# design.net
KiCad netlist of a schematic drawn in Altium Designer
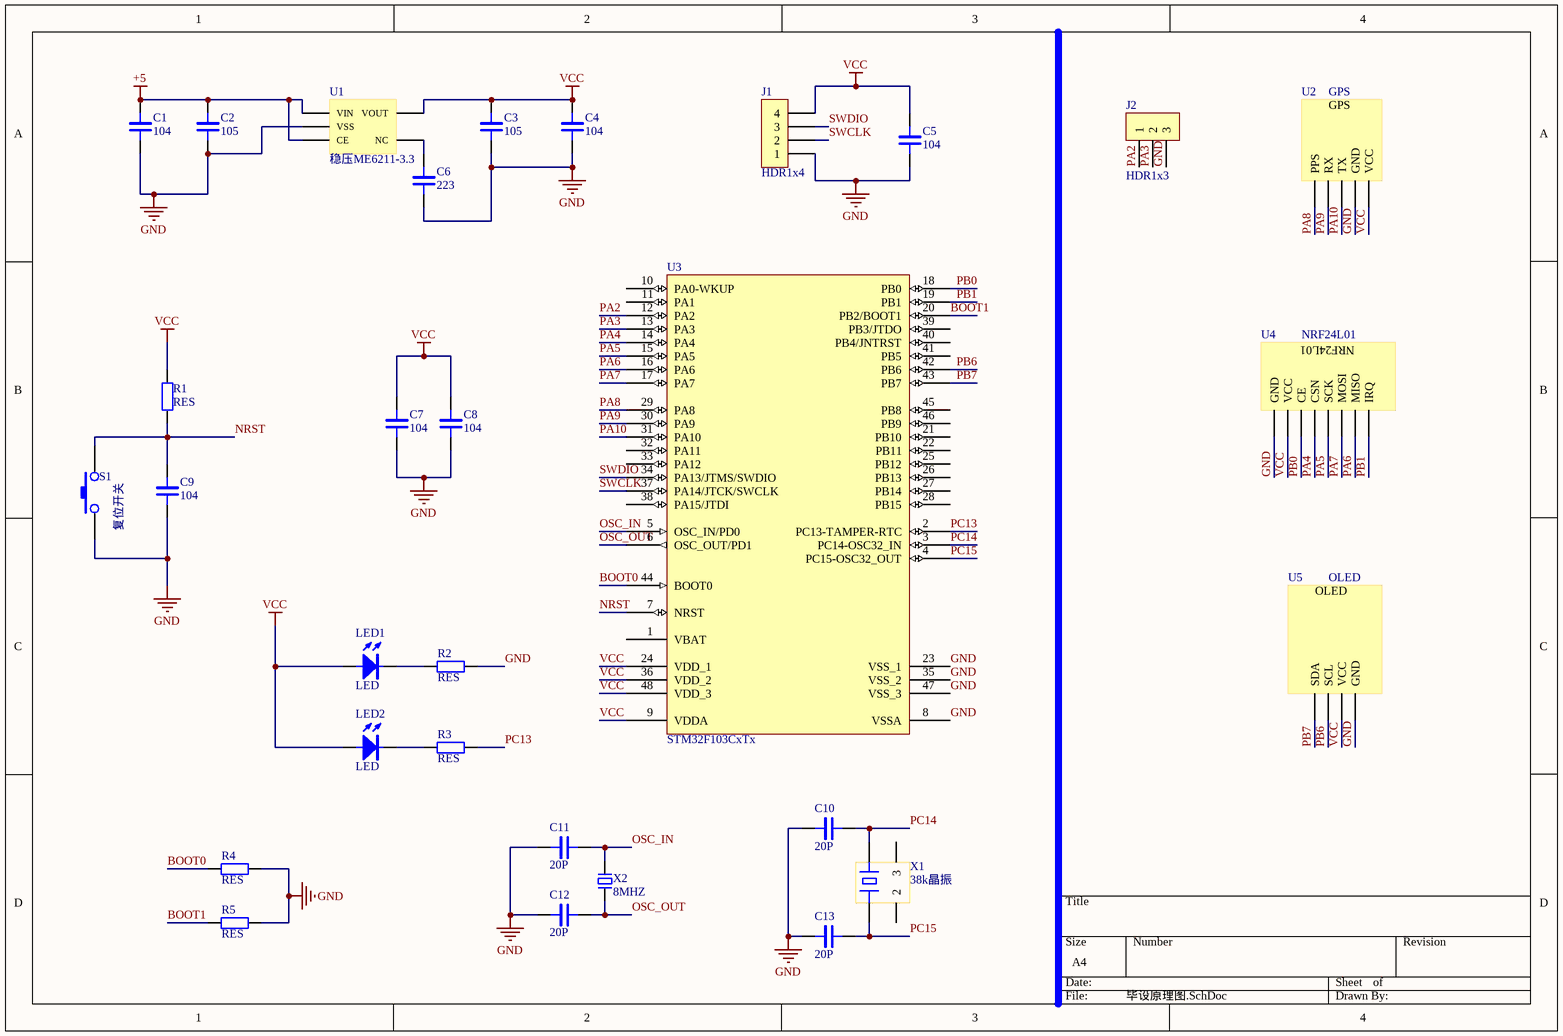
[diagram p0: 毕设原理图.SchDoc]

(export (version "E")
  (design (tool "Eeschema 10.0.6"))
  (components
    (comp (ref "C1")
      (value "104")
      (footprint "0805")
      (description "Capacitor")
      (libsource (lib "General") (part "CAP"))
    )
    (comp (ref "C2")
      (value "105")
      (footprint "0805")
      (description "Capacitor")
      (libsource (lib "General") (part "CAP"))
    )
    (comp (ref "C3")
      (value "105")
      (footprint "0805")
      (description "Capacitor")
      (libsource (lib "General") (part "CAP"))
    )
    (comp (ref "C4")
      (value "104")
      (footprint "0805")
      (description "Capacitor")
      (libsource (lib "General") (part "CAP"))
    )
    (comp (ref "C5")
      (value "104")
      (footprint "0805")
      (description "Capacitor")
      (libsource (lib "General") (part "CAP"))
    )
    (comp (ref "C6")
      (value "223")
      (footprint "0805")
      (description "Capacitor")
      (libsource (lib "General") (part "CAP"))
    )
    (comp (ref "C7")
      (value "104")
      (footprint "0805")
      (description "Capacitor")
      (libsource (lib "General") (part "CAP"))
    )
    (comp (ref "C8")
      (value "104")
      (footprint "0805")
      (description "Capacitor")
      (libsource (lib "General") (part "CAP"))
    )
    (comp (ref "C9")
      (value "104")
      (footprint "0805")
      (description "Capacitor")
      (libsource (lib "General") (part "CAP"))
    )
    (comp (ref "C10")
      (value "20P")
      (footprint "0805")
      (description "Capacitor")
      (libsource (lib "General") (part "CAP"))
    )
    (comp (ref "C11")
      (value "20P")
      (footprint "0805")
      (description "Capacitor")
      (libsource (lib "General") (part "CAP"))
    )
    (comp (ref "C12")
      (value "20P")
      (footprint "0805")
      (description "Capacitor")
      (libsource (lib "General") (part "CAP"))
    )
    (comp (ref "C13")
      (value "20P")
      (footprint "0805")
      (description "Capacitor")
      (libsource (lib "General") (part "CAP"))
    )
    (comp (ref "J1")
      (value "HDR1x4")
      (footprint "PIN-4-2.54-1.0")
      (description "Connector")
      (libsource (lib "General") (part "HDR1x4"))
    )
    (comp (ref "J2")
      (value "HDR1x3")
      (footprint "PIN-3-2.54-1.0")
      (description "Connector")
      (libsource (lib "General") (part "HDR1x3"))
    )
    (comp (ref "LED1") (value "LED") (footprint "LED-0805") (libsource (lib "General") (part "LED")))
    (comp (ref "LED2") (value "LED") (footprint "LED-0805") (libsource (lib "General") (part "LED")))
    (comp (ref "R1")
      (value "RES")
      (footprint "0805")
      (description "Resistor")
      (libsource (lib "") (part "RES_1"))
    )
    (comp (ref "R2")
      (value "RES")
      (footprint "0805")
      (description "Resistor")
      (libsource (lib "General") (part "RES"))
    )
    (comp (ref "R3")
      (value "RES")
      (footprint "0805")
      (description "Resistor")
      (libsource (lib "General") (part "RES"))
    )
    (comp (ref "R4")
      (value "RES")
      (footprint "0805")
      (description "Resistor")
      (libsource (lib "General") (part "RES"))
    )
    (comp (ref "R5")
      (value "RES")
      (footprint "0805")
      (description "Resistor")
      (libsource (lib "General") (part "RES"))
    )
    (comp (ref "S1") (value "复位开关") (footprint "按键开关") (libsource (lib "台灯集成库") (part "按键开关")))
    (comp (ref "U1")
      (value "稳压ME6211-3.3")
      (footprint "稳压ME6211-3.3")
      (libsource (lib "毕设原理图库") (part "稳压ME6211-3.3"))
    )
    (comp (ref "U2") (value "GPS") (footprint "GPS") (libsource (lib "毕设原理图库") (part "GPS")))
    (comp (ref "U3")
      (value "STM32F103CxTx")
      (footprint "QFP-48-0.5")
      (description "MCU")
      (libsource (lib "General") (part "STM32F103CxTx"))
    )
    (comp (ref "U4") (value "NRF24L01") (footprint "NRF24L01") (libsource (lib "毕设原理图库") (part "NRF24L01")))
    (comp (ref "U5") (value "OLED") (footprint "OLED") (libsource (lib "毕设原理图库") (part "OLED")))
    (comp (ref "X1") (value "38k晶振") (footprint "38k晶振") (libsource (lib "毕设原理图库") (part "38k晶振")))
    (comp (ref "X2") (value "8MHZ") (footprint "晶振1") (libsource (lib "台灯集成库") (part "晶振1（单片机）")))
  )
  (nets
    (net (code "1") (name "+5") (class "Default")
      (node (ref "C1") (pin "1") (pinfunction "1_1") (pintype "passive"))
      (node (ref "C2") (pin "1") (pinfunction "1_1") (pintype "passive"))
      (node (ref "U1") (pin "1") (pinfunction "VIN_1") (pintype "passive"))
      (node (ref "U1") (pin "3") (pinfunction "CE_3") (pintype "passive"))
    )
    (net (code "2") (name "/BOOT0") (class "Default")
      (node (ref "R4") (pin "2") (pinfunction "2_2") (pintype "passive"))
      (node (ref "U3") (pin "44") (pinfunction "BOOT0_44") (pintype "input"))
    )
    (net (code "3") (name "/BOOT1") (class "Default")
      (node (ref "R5") (pin "2") (pinfunction "2_2") (pintype "passive"))
      (node (ref "U3") (pin "20") (pinfunction "PB2/BOOT1_20") (pintype "bidirectional"))
    )
    (net (code "4") (name "/NRST") (class "Default")
      (node (ref "C9") (pin "1") (pinfunction "1_1") (pintype "passive"))
      (node (ref "R1") (pin "1") (pinfunction "1_1") (pintype "passive"))
      (node (ref "S1") (pin "2") (pinfunction "2_2") (pintype "passive"))
      (node (ref "U3") (pin "7") (pinfunction "NRST_7") (pintype "bidirectional"))
    )
    (net (code "5") (name "/OSC_IN") (class "Default")
      (node (ref "C11") (pin "2") (pinfunction "2_2") (pintype "passive"))
      (node (ref "U3") (pin "5") (pinfunction "OSC_IN/PD0_5") (pintype "input"))
      (node (ref "X2") (pin "2") (pinfunction "2_2") (pintype "passive"))
    )
    (net (code "6") (name "/OSC_OUT") (class "Default")
      (node (ref "C12") (pin "2") (pinfunction "2_2") (pintype "passive"))
      (node (ref "U3") (pin "6") (pinfunction "OSC_OUT/PD1_6") (pintype "output"))
      (node (ref "X2") (pin "1") (pinfunction "1_1") (pintype "passive"))
    )
    (net (code "7") (name "/PA2") (class "Default")
      (node (ref "J2") (pin "1") (pinfunction "1_1") (pintype "passive"))
      (node (ref "U3") (pin "12") (pinfunction "PA2_12") (pintype "bidirectional"))
    )
    (net (code "8") (name "/PA3") (class "Default")
      (node (ref "J2") (pin "2") (pinfunction "2_2") (pintype "passive"))
      (node (ref "U3") (pin "13") (pinfunction "PA3_13") (pintype "bidirectional"))
    )
    (net (code "9") (name "/PA4") (class "Default")
      (node (ref "U3") (pin "14") (pinfunction "PA4_14") (pintype "bidirectional"))
      (node (ref "U4") (pin "4") (pinfunction "CSN_4") (pintype "passive"))
    )
    (net (code "10") (name "/PA5") (class "Default")
      (node (ref "U3") (pin "15") (pinfunction "PA5_15") (pintype "bidirectional"))
      (node (ref "U4") (pin "5") (pinfunction "SCK_5") (pintype "passive"))
    )
    (net (code "11") (name "/PA6") (class "Default")
      (node (ref "U3") (pin "16") (pinfunction "PA6_16") (pintype "bidirectional"))
      (node (ref "U4") (pin "7") (pinfunction "MISO_7") (pintype "passive"))
    )
    (net (code "12") (name "/PA7") (class "Default")
      (node (ref "U3") (pin "17") (pinfunction "PA7_17") (pintype "bidirectional"))
      (node (ref "U4") (pin "6") (pinfunction "MOSI_6") (pintype "passive"))
    )
    (net (code "13") (name "/PA8") (class "Default")
      (node (ref "U2") (pin "1") (pinfunction "PPS_1") (pintype "passive"))
      (node (ref "U3") (pin "29") (pinfunction "PA8_29") (pintype "bidirectional"))
    )
    (net (code "14") (name "/PA9") (class "Default")
      (node (ref "U2") (pin "2") (pinfunction "RX_2") (pintype "passive"))
      (node (ref "U3") (pin "30") (pinfunction "PA9_30") (pintype "bidirectional"))
    )
    (net (code "15") (name "/PA10") (class "Default")
      (node (ref "U2") (pin "3") (pinfunction "TX_3") (pintype "passive"))
      (node (ref "U3") (pin "31") (pinfunction "PA10_31") (pintype "bidirectional"))
    )
    (net (code "16") (name "/PB0") (class "Default")
      (node (ref "U3") (pin "18") (pinfunction "PB0_18") (pintype "bidirectional"))
      (node (ref "U4") (pin "3") (pinfunction "CE_3") (pintype "passive"))
    )
    (net (code "17") (name "/PB1") (class "Default")
      (node (ref "U3") (pin "19") (pinfunction "PB1_19") (pintype "bidirectional"))
      (node (ref "U4") (pin "8") (pinfunction "IRQ_8") (pintype "passive"))
    )
    (net (code "18") (name "/PB6") (class "Default")
      (node (ref "U3") (pin "42") (pinfunction "PB6_42") (pintype "bidirectional"))
      (node (ref "U5") (pin "2") (pinfunction "SCL_2") (pintype "passive"))
    )
    (net (code "19") (name "/PB7") (class "Default")
      (node (ref "U3") (pin "43") (pinfunction "PB7_43") (pintype "bidirectional"))
      (node (ref "U5") (pin "1") (pinfunction "SDA_1") (pintype "passive"))
    )
    (net (code "20") (name "/PC13") (class "Default")
      (node (ref "R3") (pin "1") (pinfunction "1_1") (pintype "passive"))
      (node (ref "U3") (pin "2") (pinfunction "PC13-TAMPER-RTC_2") (pintype "bidirectional"))
    )
    (net (code "21") (name "/PC14") (class "Default")
      (node (ref "C10") (pin "2") (pinfunction "2_2") (pintype "passive"))
      (node (ref "U3") (pin "3") (pinfunction "PC14-OSC32_IN_3") (pintype "bidirectional"))
      (node (ref "X1") (pin "4") (pinfunction "4_4") (pintype "passive"))
    )
    (net (code "22") (name "/PC15") (class "Default")
      (node (ref "C13") (pin "2") (pinfunction "2_2") (pintype "passive"))
      (node (ref "U3") (pin "4") (pinfunction "PC15-OSC32_OUT_4") (pintype "bidirectional"))
      (node (ref "X1") (pin "1") (pinfunction "1_1") (pintype "passive"))
    )
    (net (code "23") (name "/SWCLK") (class "Default")
      (node (ref "J1") (pin "2") (pinfunction "2_2") (pintype "passive"))
      (node (ref "U3") (pin "37") (pinfunction "PA14/JTCK/SWCLK_37") (pintype "bidirectional"))
    )
    (net (code "24") (name "/SWDIO") (class "Default")
      (node (ref "J1") (pin "3") (pinfunction "3_3") (pintype "passive"))
      (node (ref "U3") (pin "34") (pinfunction "PA13/JTMS/SWDIO_34") (pintype "bidirectional"))
    )
    (net (code "25") (name "GND") (class "Default")
      (node (ref "C1") (pin "2") (pinfunction "2_2") (pintype "passive"))
      (node (ref "C10") (pin "1") (pinfunction "1_1") (pintype "passive"))
      (node (ref "C11") (pin "1") (pinfunction "1_1") (pintype "passive"))
      (node (ref "C12") (pin "1") (pinfunction "1_1") (pintype "passive"))
      (node (ref "C13") (pin "1") (pinfunction "1_1") (pintype "passive"))
      (node (ref "C2") (pin "2") (pinfunction "2_2") (pintype "passive"))
      (node (ref "C3") (pin "2") (pinfunction "2_2") (pintype "passive"))
      (node (ref "C4") (pin "2") (pinfunction "2_2") (pintype "passive"))
      (node (ref "C5") (pin "2") (pinfunction "2_2") (pintype "passive"))
      (node (ref "C6") (pin "2") (pinfunction "2_2") (pintype "passive"))
      (node (ref "C7") (pin "2") (pinfunction "2_2") (pintype "passive"))
      (node (ref "C8") (pin "2") (pinfunction "2_2") (pintype "passive"))
      (node (ref "C9") (pin "2") (pinfunction "2_2") (pintype "passive"))
      (node (ref "J1") (pin "1") (pinfunction "1_1") (pintype "passive"))
      (node (ref "J2") (pin "3") (pinfunction "3_3") (pintype "passive"))
      (node (ref "R2") (pin "1") (pinfunction "1_1") (pintype "passive"))
      (node (ref "R4") (pin "1") (pinfunction "1_1") (pintype "passive"))
      (node (ref "R5") (pin "1") (pinfunction "1_1") (pintype "passive"))
      (node (ref "S1") (pin "1") (pinfunction "1_1") (pintype "passive"))
      (node (ref "U1") (pin "2") (pinfunction "VSS_2") (pintype "passive"))
      (node (ref "U2") (pin "4") (pinfunction "GND_4") (pintype "passive"))
      (node (ref "U3") (pin "23") (pinfunction "VSS_1_23") (pintype "power_in"))
      (node (ref "U3") (pin "35") (pinfunction "VSS_2_35") (pintype "power_in"))
      (node (ref "U3") (pin "47") (pinfunction "VSS_3_47") (pintype "power_in"))
      (node (ref "U3") (pin "8") (pinfunction "VSSA_8") (pintype "power_in"))
      (node (ref "U4") (pin "1") (pinfunction "GND_1") (pintype "passive"))
      (node (ref "U5") (pin "4") (pinfunction "GND_4") (pintype "passive"))
    )
    (net (code "26") (name "Net-(LED1-C)") (class "Default")
      (node (ref "LED1") (pin "2") (pinfunction "C_2") (pintype "passive"))
      (node (ref "R2") (pin "2") (pinfunction "2_2") (pintype "passive"))
    )
    (net (code "27") (name "Net-(LED2-C)") (class "Default")
      (node (ref "LED2") (pin "2") (pinfunction "C_2") (pintype "passive"))
      (node (ref "R3") (pin "2") (pinfunction "2_2") (pintype "passive"))
    )
    (net (code "28") (name "Net-(U1-NC)") (class "Default")
      (node (ref "C6") (pin "1") (pinfunction "1_1") (pintype "passive"))
      (node (ref "U1") (pin "4") (pinfunction "NC_4") (pintype "passive"))
    )
    (net (code "29") (name "VCC") (class "Default")
      (node (ref "C3") (pin "1") (pinfunction "1_1") (pintype "passive"))
      (node (ref "C4") (pin "1") (pinfunction "1_1") (pintype "passive"))
      (node (ref "C5") (pin "1") (pinfunction "1_1") (pintype "passive"))
      (node (ref "C7") (pin "1") (pinfunction "1_1") (pintype "passive"))
      (node (ref "C8") (pin "1") (pinfunction "1_1") (pintype "passive"))
      (node (ref "J1") (pin "4") (pinfunction "4_4") (pintype "passive"))
      (node (ref "LED1") (pin "1") (pinfunction "A_1") (pintype "passive"))
      (node (ref "LED2") (pin "1") (pinfunction "A_1") (pintype "passive"))
      (node (ref "R1") (pin "2") (pinfunction "2_2") (pintype "passive"))
      (node (ref "U1") (pin "5") (pinfunction "VOUT_5") (pintype "passive"))
      (node (ref "U2") (pin "5") (pinfunction "VCC_5") (pintype "passive"))
      (node (ref "U3") (pin "24") (pinfunction "VDD_1_24") (pintype "power_in"))
      (node (ref "U3") (pin "36") (pinfunction "VDD_2_36") (pintype "power_in"))
      (node (ref "U3") (pin "48") (pinfunction "VDD_3_48") (pintype "power_in"))
      (node (ref "U3") (pin "9") (pinfunction "VDDA_9") (pintype "power_in"))
      (node (ref "U4") (pin "2") (pinfunction "VCC_2") (pintype "passive"))
      (node (ref "U5") (pin "3") (pinfunction "VCC_3") (pintype "passive"))
    )
    (net (code "30") (name "unconnected-(U3-PA0-WKUP-Pad10)") (class "Default")
      (node (ref "U3") (pin "10") (pinfunction "PA0-WKUP_10") (pintype "bidirectional"))
    )
    (net (code "31") (name "unconnected-(U3-PA1-Pad11)") (class "Default")
      (node (ref "U3") (pin "11") (pinfunction "PA1_11") (pintype "bidirectional"))
    )
    (net (code "32") (name "unconnected-(U3-PA11-Pad32)") (class "Default")
      (node (ref "U3") (pin "32") (pinfunction "PA11_32") (pintype "bidirectional"))
    )
    (net (code "33") (name "unconnected-(U3-PA12-Pad33)") (class "Default")
      (node (ref "U3") (pin "33") (pinfunction "PA12_33") (pintype "bidirectional"))
    )
    (net (code "34") (name "unconnected-(U3-PA15{slash}JTDI-Pad38)") (class "Default")
      (node (ref "U3") (pin "38") (pinfunction "PA15/JTDI_38") (pintype "bidirectional"))
    )
    (net (code "35") (name "unconnected-(U3-PB3{slash}JTDO-Pad39)") (class "Default")
      (node (ref "U3") (pin "39") (pinfunction "PB3/JTDO_39") (pintype "bidirectional"))
    )
    (net (code "36") (name "unconnected-(U3-PB4{slash}JNTRST-Pad40)") (class "Default")
      (node (ref "U3") (pin "40") (pinfunction "PB4/JNTRST_40") (pintype "bidirectional"))
    )
    (net (code "37") (name "unconnected-(U3-PB5-Pad41)") (class "Default")
      (node (ref "U3") (pin "41") (pinfunction "PB5_41") (pintype "bidirectional"))
    )
    (net (code "38") (name "unconnected-(U3-PB8-Pad45)") (class "Default")
      (node (ref "U3") (pin "45") (pinfunction "PB8_45") (pintype "bidirectional"))
    )
    (net (code "39") (name "unconnected-(U3-PB9-Pad46)") (class "Default")
      (node (ref "U3") (pin "46") (pinfunction "PB9_46") (pintype "bidirectional"))
    )
    (net (code "40") (name "unconnected-(U3-PB10-Pad21)") (class "Default")
      (node (ref "U3") (pin "21") (pinfunction "PB10_21") (pintype "bidirectional"))
    )
    (net (code "41") (name "unconnected-(U3-PB11-Pad22)") (class "Default")
      (node (ref "U3") (pin "22") (pinfunction "PB11_22") (pintype "bidirectional"))
    )
    (net (code "42") (name "unconnected-(U3-PB12-Pad25)") (class "Default")
      (node (ref "U3") (pin "25") (pinfunction "PB12_25") (pintype "bidirectional"))
    )
    (net (code "43") (name "unconnected-(U3-PB13-Pad26)") (class "Default")
      (node (ref "U3") (pin "26") (pinfunction "PB13_26") (pintype "bidirectional"))
    )
    (net (code "44") (name "unconnected-(U3-PB14-Pad27)") (class "Default")
      (node (ref "U3") (pin "27") (pinfunction "PB14_27") (pintype "bidirectional"))
    )
    (net (code "45") (name "unconnected-(U3-PB15-Pad28)") (class "Default")
      (node (ref "U3") (pin "28") (pinfunction "PB15_28") (pintype "bidirectional"))
    )
    (net (code "46") (name "unconnected-(U3-VBAT-Pad1)") (class "Default")
      (node (ref "U3") (pin "1") (pinfunction "VBAT_1") (pintype "power_in"))
    )
    (net (code "47") (name "unconnected-(X1-Pad2)") (class "Default")
      (node (ref "X1") (pin "2") (pinfunction "2_2") (pintype "passive"))
    )
    (net (code "48") (name "unconnected-(X1-Pad3)") (class "Default")
      (node (ref "X1") (pin "3") (pinfunction "3_3") (pintype "passive"))
    )
  )
)
